# ATtiny_badge.net
KiCad netlist of a schematic drawn in EAGLE
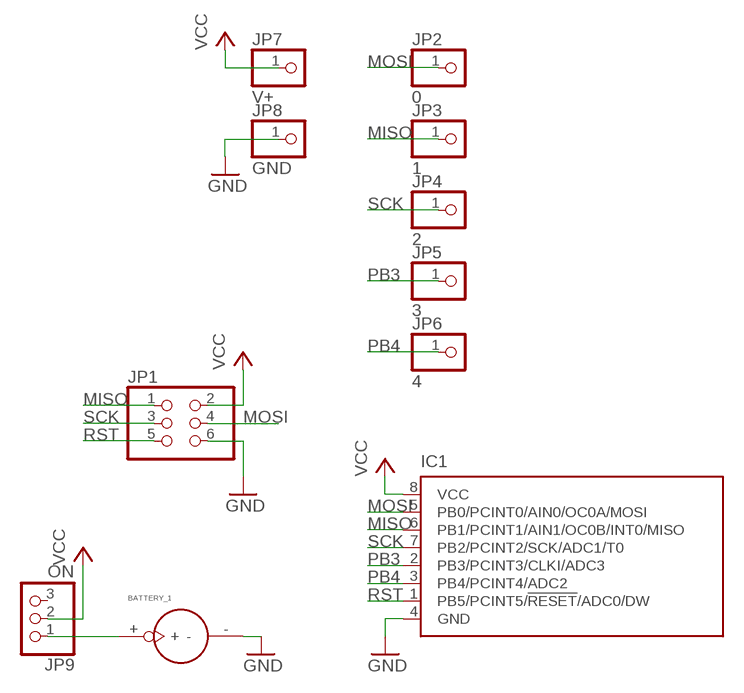
[diagram p0: schematic, sheet 1]

(export (version "E")
  (design (tool "Eeschema 10.0.6"))
  (components
    (comp (ref "BATTERY_1")
      (value "BATTERY_1236_C")
      (footprint "eagle-import:BATTERY_1236_C")
      (libsource (lib "eagle-import") (part "BATTERY_1236_C"))
    )
    (comp (ref "IC1")
      (value "TINY13-20SU")
      (footprint "eagle-import:8S2")
      (fields (field (name "MPN") "ATTINY13-20SU"))
      (libsource (lib "eagle-import") (part "TINY13SU-20"))
    )
    (comp (ref "JP1")
      (value "PINHD-2X3")
      (footprint "eagle-import:2X03")
      (libsource (lib "eagle-import") (part "PINHD-2X3"))
    )
    (comp (ref "JP2")
      (value "0")
      (footprint "eagle-import:1X01")
      (libsource (lib "eagle-import") (part "PINHD-1X1"))
    )
    (comp (ref "JP3")
      (value "1")
      (footprint "eagle-import:1X01")
      (libsource (lib "eagle-import") (part "PINHD-1X1"))
    )
    (comp (ref "JP4")
      (value "2")
      (footprint "eagle-import:1X01")
      (libsource (lib "eagle-import") (part "PINHD-1X1"))
    )
    (comp (ref "JP5")
      (value "3")
      (footprint "eagle-import:1X01")
      (libsource (lib "eagle-import") (part "PINHD-1X1"))
    )
    (comp (ref "JP6")
      (value "4")
      (footprint "eagle-import:1X01")
      (libsource (lib "eagle-import") (part "PINHD-1X1"))
    )
    (comp (ref "JP7")
      (value "V+")
      (footprint "eagle-import:1X01")
      (libsource (lib "eagle-import") (part "PINHD-1X1"))
    )
    (comp (ref "JP8")
      (value "GND")
      (footprint "eagle-import:1X01")
      (libsource (lib "eagle-import") (part "PINHD-1X1"))
    )
    (comp (ref "JP9")
      (value "ON")
      (footprint "eagle-import:1X03")
      (libsource (lib "eagle-import") (part "PINHD-1X3"))
    )
  )
  (nets
    (net (code "1") (name "/MISO") (class "Default")
      (node (ref "IC1") (pin "6") (pinfunction "PB1/PCINT1/AIN1/OC0B/INT0/MISO_6") (pintype "bidirectional"))
      (node (ref "JP1") (pin "1") (pinfunction "1_1") (pintype "passive"))
      (node (ref "JP3") (pin "1") (pinfunction "1_1") (pintype "passive"))
    )
    (net (code "2") (name "/MOSI") (class "Default")
      (node (ref "IC1") (pin "5") (pinfunction "PB0/PCINT0/AIN0/OC0A/MOSI_5") (pintype "bidirectional"))
      (node (ref "JP1") (pin "4") (pinfunction "4_4") (pintype "passive"))
      (node (ref "JP2") (pin "1") (pinfunction "1_1") (pintype "passive"))
    )
    (net (code "3") (name "/PB3") (class "Default")
      (node (ref "IC1") (pin "2") (pinfunction "PB3/PCINT3/CLKI/ADC3_2") (pintype "bidirectional"))
      (node (ref "JP5") (pin "1") (pinfunction "1_1") (pintype "passive"))
    )
    (net (code "4") (name "/PB4") (class "Default")
      (node (ref "IC1") (pin "3") (pinfunction "PB4/PCINT4/ADC2_3") (pintype "bidirectional"))
      (node (ref "JP6") (pin "1") (pinfunction "1_1") (pintype "passive"))
    )
    (net (code "5") (name "/RST") (class "Default")
      (node (ref "IC1") (pin "1") (pinfunction "PB5/PCINT5/~{RESET}/ADC0/DW_1") (pintype "bidirectional"))
      (node (ref "JP1") (pin "5") (pinfunction "5_5") (pintype "passive"))
    )
    (net (code "6") (name "/SCK") (class "Default")
      (node (ref "IC1") (pin "7") (pinfunction "PB2/PCINT2/SCK/ADC1/T0_7") (pintype "bidirectional"))
      (node (ref "JP1") (pin "3") (pinfunction "3_3") (pintype "passive"))
      (node (ref "JP4") (pin "1") (pinfunction "1_1") (pintype "passive"))
    )
    (net (code "7") (name "GND") (class "Default")
      (node (ref "BATTERY_1") (pin "-") (pinfunction "-_-") (pintype "bidirectional"))
      (node (ref "IC1") (pin "4") (pinfunction "GND_4") (pintype "power_in"))
      (node (ref "JP1") (pin "6") (pinfunction "6_6") (pintype "passive"))
      (node (ref "JP8") (pin "1") (pinfunction "1_1") (pintype "passive"))
    )
    (net (code "8") (name "Net-(BATTERY_1-Pad+)") (class "Default")
      (node (ref "BATTERY_1") (pin "+") (pinfunction "+_+") (pintype "bidirectional"))
      (node (ref "JP9") (pin "1") (pinfunction "1_1") (pintype "passive"))
    )
    (net (code "9") (name "VCC") (class "Default")
      (node (ref "IC1") (pin "8") (pinfunction "VCC_8") (pintype "power_in"))
      (node (ref "JP1") (pin "2") (pinfunction "2_2") (pintype "passive"))
      (node (ref "JP7") (pin "1") (pinfunction "1_1") (pintype "passive"))
      (node (ref "JP9") (pin "2") (pinfunction "2_2") (pintype "passive"))
    )
    (net (code "10") (name "unconnected-(JP9-Pad3)") (class "Default")
      (node (ref "JP9") (pin "3") (pinfunction "3_3") (pintype "passive"))
    )
  )
)
